# Sheet3.net
KiCad netlist of a schematic drawn in Altium Designer
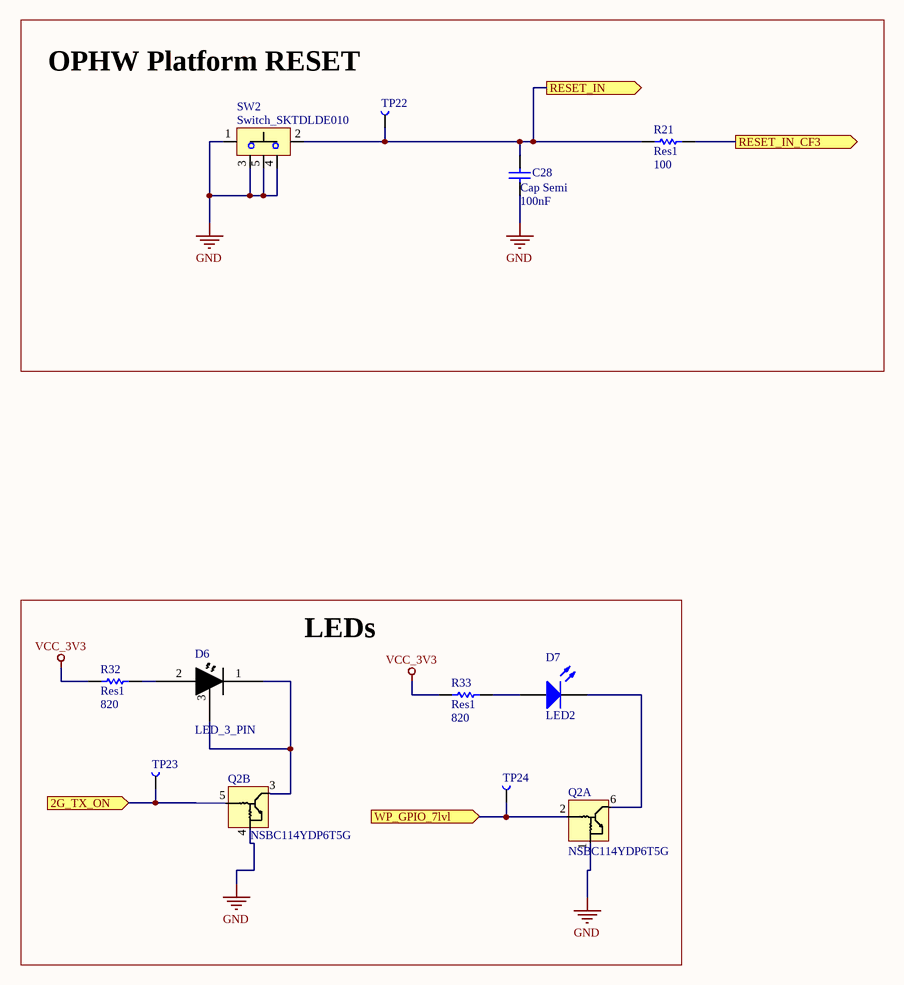
[diagram p0: Sheet3.SchDoc]

(export (version "E")
  (design (tool "Eeschema 10.0.6"))
  (components
    (comp (ref "C28")
      (value "Cap Semi")
      (footprint "CAP 0402/1005")
      (description "0.1µF -20%, +80% 16V Ceramic Capacitor Y5V (F) 0402 (1005 Metric)")
      (fields (field (name "PART NUMBER") "VJ0402V104ZXJCW1BC") (field (name "ALTIUM_VALUE") "100nF"))
      (libsource (lib "Miscellaneous Devices") (part "Cap Semi"))
    )
    (comp (ref "D6")
      (value "LED_3_PIN")
      (footprint "LED_3_PIN")
      (description "Yellow-Green 573nm LED Indication - Discrete 2V 2-SMD, No Lead")
      (fields (field (name "PART NUMBER") "12-21SYGC/S530-E2/TR8"))
      (libsource (lib "LED_3_PIN") (part "LED_3_PIN"))
    )
    (comp (ref "D7")
      (value "LED2")
      (footprint "LED_0603 - 3D")
      (description "Green  LED Indication - Discrete 2.2V 0603 (1608 Metric)")
      (fields (field (name "PART NUMBER") "SML-310MTT86") (field (name "PUBLISHER") "Altium Limited"))
      (libsource (lib "Miscellaneous Devices") (part "LED2"))
    )
    (comp (ref "Q2")
      (value "NSBC114YDP6T5G")
      (footprint "NSBC114YDP6T5G")
      (libsource (lib "") (part "NSBC114YDP6T5G_1"))
    )
    (comp (ref "R21")
      (value "Res1")
      (footprint "RES 0402/1005")
      (description "100 Ohms ±5% 0.063W, 1/16W Chip Resistor 0402 (1005 Metric) Automotive AEC-Q200 Thick Film")
      (fields (field (name "PART NUMBER") "MCR01MZPJ101") (field (name "ALTIUM_VALUE") "100"))
      (libsource (lib "Miscellaneous Devices") (part "Res1"))
    )
    (comp (ref "R32")
      (value "Res1")
      (footprint "RES 0402/1005")
      (description "820 Ohms ±5% 0.1W, 1/10W Chip Resistor 0402 (1005 Metric) Automotive AEC-Q200 Thick Film")
      (fields (field (name "PART NUMBER") "RK73B1ETTP821J") (field (name "ALTIUM_VALUE") "820"))
      (libsource (lib "Miscellaneous Devices") (part "Res1"))
    )
    (comp (ref "R33")
      (value "Res1")
      (footprint "RES 0402/1005")
      (description "820 Ohms ±5% 0.1W, 1/10W Chip Resistor 0402 (1005 Metric) Automotive AEC-Q200 Thick Film")
      (fields (field (name "PART NUMBER") "RK73B1ETTP821J") (field (name "ALTIUM_VALUE") "820"))
      (libsource (lib "Miscellaneous Devices") (part "Res1"))
    )
    (comp (ref "SW2")
      (value "Switch_SKTDLDE010")
      (footprint "Switch_SKTDLDE010")
      (description "Tactile Switches Tact Switch")
      (fields (field (name "PART NUMBER") "SKTDLDE010"))
      (libsource (lib "Switch_SKTDLDE010") (part "Switch_SKTDLDE010"))
    )
    (comp (ref "TP22")
      (value "TestPoint")
      (footprint "TestPoint")
      (libsource (lib "TestPoint") (part "TestPoint"))
    )
    (comp (ref "TP23")
      (value "TestPoint")
      (footprint "TestPoint")
      (libsource (lib "TestPoint") (part "TestPoint"))
    )
    (comp (ref "TP24")
      (value "TestPoint")
      (footprint "TestPoint")
      (libsource (lib "TestPoint") (part "TestPoint"))
    )
  )
  (nets
    (net (code "1") (name "/2G_TX_ON") (class "Default")
      (node (ref "Q2") (pin "5") (pintype "passive"))
      (node (ref "TP23") (pin "1") (pinfunction "TP_1") (pintype "passive"))
    )
    (net (code "2") (name "/RESET_IN") (class "Default")
      (node (ref "C28") (pin "2") (pinfunction "2_2") (pintype "passive"))
      (node (ref "R21") (pin "1") (pinfunction "1_1") (pintype "passive"))
      (node (ref "SW2") (pin "2") (pintype "passive"))
      (node (ref "TP22") (pin "1") (pinfunction "TP_1") (pintype "passive"))
    )
    (net (code "3") (name "/RESET_IN_CF3") (class "Default")
      (node (ref "R21") (pin "2") (pinfunction "2_2") (pintype "passive"))
    )
    (net (code "4") (name "/WP_GPIO_7lvl") (class "Default")
      (node (ref "Q2") (pin "2") (pintype "passive"))
      (node (ref "TP24") (pin "1") (pinfunction "TP_1") (pintype "passive"))
    )
    (net (code "5") (name "GND") (class "Default")
      (node (ref "C28") (pin "1") (pinfunction "1_1") (pintype "passive"))
      (node (ref "Q2") (pin "1") (pintype "passive"))
      (node (ref "Q2") (pin "4") (pintype "passive"))
      (node (ref "SW2") (pin "1") (pintype "passive"))
      (node (ref "SW2") (pin "3") (pintype "passive"))
      (node (ref "SW2") (pin "4") (pintype "passive"))
      (node (ref "SW2") (pin "5") (pintype "passive"))
    )
    (net (code "6") (name "Net-(D6-Pad1)") (class "Default")
      (node (ref "D6") (pin "1") (pintype "passive"))
      (node (ref "D6") (pin "3") (pintype "passive"))
      (node (ref "Q2") (pin "3") (pintype "passive"))
    )
    (net (code "7") (name "Net-(D6-Pad2)") (class "Default")
      (node (ref "D6") (pin "2") (pintype "passive"))
      (node (ref "R32") (pin "1") (pinfunction "1_1") (pintype "passive"))
    )
    (net (code "8") (name "Net-(D7-A)") (class "Default")
      (node (ref "D7") (pin "1") (pinfunction "A_1") (pintype "passive"))
      (node (ref "R33") (pin "1") (pinfunction "1_1") (pintype "passive"))
    )
    (net (code "9") (name "Net-(D7-K)") (class "Default")
      (node (ref "D7") (pin "2") (pinfunction "K_2") (pintype "passive"))
      (node (ref "Q2") (pin "6") (pintype "passive"))
    )
    (net (code "10") (name "VCC_3V3") (class "Default")
      (node (ref "R32") (pin "2") (pinfunction "2_2") (pintype "passive"))
      (node (ref "R33") (pin "2") (pinfunction "2_2") (pintype "passive"))
    )
  )
)
